# tiltGame.net
KiCad netlist of a schematic drawn in EAGLE
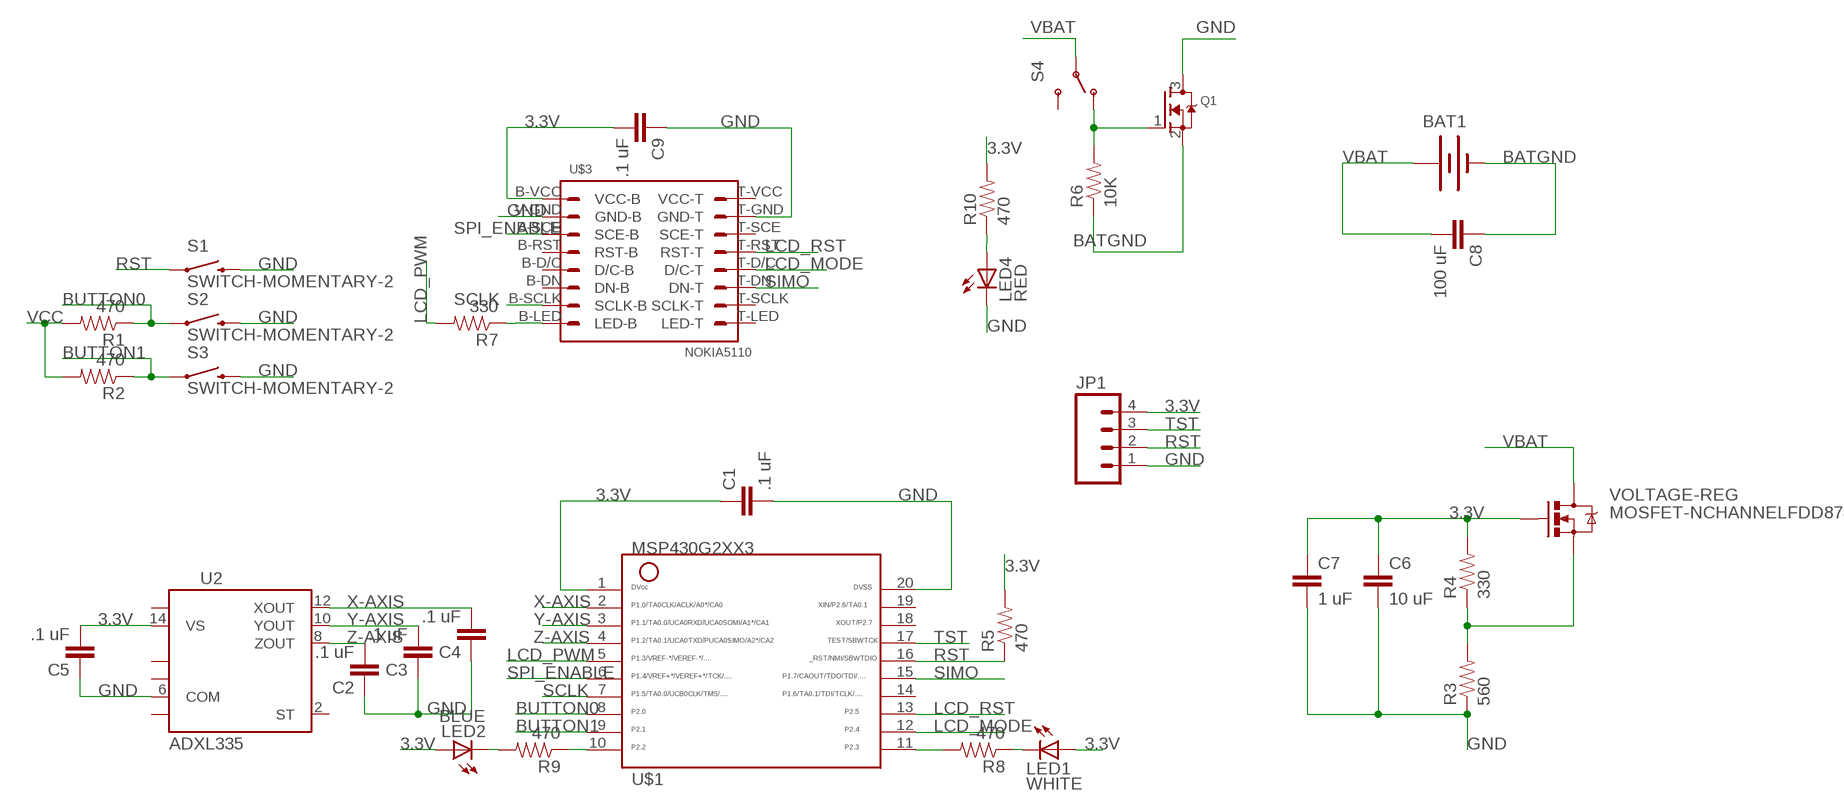
[diagram p0: schematic, sheet 1]

(export (version "E")
  (design (tool "Eeschema 10.0.6"))
  (components
    (comp (ref "BAT1")
      (value "BATTERY9V")
      (footprint "eagle-import:BATTCON_9V")
      (libsource (lib "eagle-import") (part "BATTERY9V"))
    )
    (comp (ref "C1")
      (value ".1 uF")
      (footprint "eagle-import:0805")
      (libsource (lib "eagle-import") (part "CAP0805"))
    )
    (comp (ref "C2")
      (value ".1 uF")
      (footprint "eagle-import:0805")
      (libsource (lib "eagle-import") (part "CAP0805"))
    )
    (comp (ref "C3")
      (value ".1 uF")
      (footprint "eagle-import:0805")
      (libsource (lib "eagle-import") (part "CAP0805"))
    )
    (comp (ref "C4")
      (value ".1 uF")
      (footprint "eagle-import:0805")
      (libsource (lib "eagle-import") (part "CAP0805"))
    )
    (comp (ref "C5")
      (value ".1 uF")
      (footprint "eagle-import:0805")
      (libsource (lib "eagle-import") (part "CAP0805"))
    )
    (comp (ref "C6")
      (value "10 uF")
      (footprint "eagle-import:0805")
      (libsource (lib "eagle-import") (part "CAP0805"))
    )
    (comp (ref "C7")
      (value "1 uF")
      (footprint "eagle-import:0805")
      (libsource (lib "eagle-import") (part "CAP0805"))
    )
    (comp (ref "C8")
      (value "100 uF")
      (footprint "eagle-import:0805")
      (libsource (lib "eagle-import") (part "CAP0805"))
    )
    (comp (ref "C9")
      (value ".1 uF")
      (footprint "eagle-import:0805")
      (libsource (lib "eagle-import") (part "CAP0805"))
    )
    (comp (ref "JP1")
      (value "M041X04_NO_SILK")
      (footprint "eagle-import:1X04_NO_SILK")
      (libsource (lib "eagle-import") (part "M041X04_NO_SILK"))
    )
    (comp (ref "LED1")
      (value "WHITE")
      (footprint "eagle-import:LED-1206")
      (libsource (lib "eagle-import") (part "LED1206"))
    )
    (comp (ref "LED2")
      (value "BLUE")
      (footprint "eagle-import:LED-1206")
      (libsource (lib "eagle-import") (part "LED1206"))
    )
    (comp (ref "LED4")
      (value "RED")
      (footprint "eagle-import:LED-1206")
      (libsource (lib "eagle-import") (part "LED1206"))
    )
    (comp (ref "Q1")
      (value "MOSFET-NWAVE")
      (footprint "eagle-import:SOT23-W")
      (libsource (lib "eagle-import") (part "MOSFET-NWAVE"))
    )
    (comp (ref "R1")
      (value "470")
      (footprint "eagle-import:0805")
      (libsource (lib "eagle-import") (part "RESISTOR0805-RES"))
    )
    (comp (ref "R2")
      (value "470")
      (footprint "eagle-import:0805")
      (libsource (lib "eagle-import") (part "RESISTOR0805-RES"))
    )
    (comp (ref "R3")
      (value "560")
      (footprint "eagle-import:0805")
      (libsource (lib "eagle-import") (part "RESISTOR0805-RES"))
    )
    (comp (ref "R4")
      (value "330")
      (footprint "eagle-import:0805")
      (libsource (lib "eagle-import") (part "RESISTOR0805-RES"))
    )
    (comp (ref "R5")
      (value "470")
      (footprint "eagle-import:0805")
      (libsource (lib "eagle-import") (part "RESISTOR0805-RES"))
    )
    (comp (ref "R6")
      (value "10K")
      (footprint "eagle-import:0805")
      (libsource (lib "eagle-import") (part "RESISTOR0805-RES"))
    )
    (comp (ref "R7")
      (value "330")
      (footprint "eagle-import:0805")
      (libsource (lib "eagle-import") (part "RESISTOR0805-RES"))
    )
    (comp (ref "R8")
      (value "470")
      (footprint "eagle-import:0805")
      (libsource (lib "eagle-import") (part "RESISTOR0805-RES"))
    )
    (comp (ref "R9")
      (value "470")
      (footprint "eagle-import:0805")
      (libsource (lib "eagle-import") (part "RESISTOR0805-RES"))
    )
    (comp (ref "R10")
      (value "470")
      (footprint "eagle-import:0805")
      (libsource (lib "eagle-import") (part "RESISTOR0805-RES"))
    )
    (comp (ref "S1")
      (value "SWITCH-MOMENTARY-2")
      (footprint "eagle-import:TACTILE_PANISONIC")
      (libsource (lib "eagle-import") (part "SWITCH-MOMENTARY-2"))
    )
    (comp (ref "S2")
      (value "SWITCH-MOMENTARY-2")
      (footprint "eagle-import:TACTILE_PANISONIC")
      (libsource (lib "eagle-import") (part "SWITCH-MOMENTARY-2"))
    )
    (comp (ref "S3")
      (value "SWITCH-MOMENTARY-2")
      (footprint "eagle-import:TACTILE_PANISONIC")
      (libsource (lib "eagle-import") (part "SWITCH-MOMENTARY-2"))
    )
    (comp (ref "S4")
      (value "SWITCH-SPDTPTH")
      (footprint "eagle-import:SWITCH-SPDT")
      (libsource (lib "eagle-import") (part "SWITCH-SPDTPTH"))
    )
    (comp (ref "U$1")
      (value "MSP430G2XX3TSSOP")
      (footprint "eagle-import:PW20")
      (libsource (lib "eagle-import") (part "MSP430G2XX3TSSOP"))
    )
    (comp (ref "U$3")
      (value "NOKIA5110")
      (footprint "eagle-import:NOKIA5110")
      (libsource (lib "eagle-import") (part "NOKIA5110"))
    )
    (comp (ref "U2")
      (value "ADXL335")
      (footprint "eagle-import:LFCSP-16")
      (libsource (lib "eagle-import") (part "ADXL335"))
    )
    (comp (ref "VOLTAGE-REG")
      (value "MOSFET-NCHANNELFDD8780")
      (footprint "eagle-import:DPAK")
      (libsource (lib "eagle-import") (part "MOSFET-NCHANNELFDD8780"))
    )
  )
  (nets
    (net (code "1") (name "/3.3V") (class "Default")
      (node (ref "C1") (pin "1") (pinfunction "1_1") (pintype "passive"))
      (node (ref "C5") (pin "2") (pinfunction "2_2") (pintype "passive"))
      (node (ref "C6") (pin "1") (pinfunction "1_1") (pintype "passive"))
      (node (ref "C7") (pin "1") (pinfunction "1_1") (pintype "passive"))
      (node (ref "C9") (pin "2") (pinfunction "2_2") (pintype "passive"))
      (node (ref "JP1") (pin "4") (pinfunction "4_4") (pintype "passive"))
      (node (ref "LED1") (pin "A") (pinfunction "A_A") (pintype "passive"))
      (node (ref "LED2") (pin "A") (pinfunction "A_A") (pintype "passive"))
      (node (ref "R10") (pin "2") (pinfunction "2_2") (pintype "passive"))
      (node (ref "R4") (pin "2") (pinfunction "2_2") (pintype "passive"))
      (node (ref "R5") (pin "2") (pinfunction "2_2") (pintype "passive"))
      (node (ref "U$1") (pin "1") (pinfunction "1_1") (pintype "bidirectional"))
      (node (ref "U$3") (pin "B-VCC") (pinfunction "VCC-B_B-VCC") (pintype "bidirectional"))
      (node (ref "U2") (pin "14") (pinfunction "VS_14") (pintype "bidirectional"))
      (node (ref "VOLTAGE-REG") (pin "3") (pinfunction "G-3_3") (pintype "passive"))
    )
    (net (code "2") (name "/BATGND") (class "Default")
      (node (ref "BAT1") (pin "-") (pinfunction "-_-") (pintype "power_in"))
      (node (ref "C8") (pin "1") (pinfunction "1_1") (pintype "passive"))
      (node (ref "Q1") (pin "2") (pinfunction "S_2") (pintype "bidirectional"))
      (node (ref "R6") (pin "1") (pinfunction "1_1") (pintype "passive"))
    )
    (net (code "3") (name "/BUTTON0") (class "Default")
      (node (ref "R1") (pin "1") (pinfunction "1_1") (pintype "passive"))
      (node (ref "S2") (pin "1") (pinfunction "1_1") (pintype "passive"))
      (node (ref "U$1") (pin "8") (pinfunction "8_8") (pintype "bidirectional"))
    )
    (net (code "4") (name "/BUTTON1") (class "Default")
      (node (ref "R2") (pin "1") (pinfunction "1_1") (pintype "passive"))
      (node (ref "S3") (pin "1") (pinfunction "1_1") (pintype "passive"))
      (node (ref "U$1") (pin "9") (pinfunction "9_9") (pintype "bidirectional"))
    )
    (net (code "5") (name "/GND") (class "Default")
      (node (ref "C1") (pin "2") (pinfunction "2_2") (pintype "passive"))
      (node (ref "C2") (pin "1") (pinfunction "1_1") (pintype "passive"))
      (node (ref "C3") (pin "1") (pinfunction "1_1") (pintype "passive"))
      (node (ref "C4") (pin "1") (pinfunction "1_1") (pintype "passive"))
      (node (ref "C5") (pin "1") (pinfunction "1_1") (pintype "passive"))
      (node (ref "C6") (pin "2") (pinfunction "2_2") (pintype "passive"))
      (node (ref "C7") (pin "2") (pinfunction "2_2") (pintype "passive"))
      (node (ref "C9") (pin "1") (pinfunction "1_1") (pintype "passive"))
      (node (ref "JP1") (pin "1") (pinfunction "1_1") (pintype "passive"))
      (node (ref "LED4") (pin "C") (pinfunction "C_C") (pintype "passive"))
      (node (ref "Q1") (pin "3") (pinfunction "D_3") (pintype "bidirectional"))
      (node (ref "R3") (pin "1") (pinfunction "1_1") (pintype "passive"))
      (node (ref "S1") (pin "2") (pinfunction "2_2") (pintype "passive"))
      (node (ref "S2") (pin "2") (pinfunction "2_2") (pintype "passive"))
      (node (ref "S3") (pin "2") (pinfunction "2_2") (pintype "passive"))
      (node (ref "U$1") (pin "20") (pinfunction "20_20") (pintype "bidirectional"))
      (node (ref "U$3") (pin "T-GND") (pinfunction "GND-T_T-GND") (pintype "bidirectional"))
      (node (ref "U$3") (pin "V-GND") (pinfunction "GND-B_V-GND") (pintype "bidirectional"))
      (node (ref "U2") (pin "6") (pinfunction "COM_6") (pintype "bidirectional"))
    )
    (net (code "6") (name "/LCD_MODE") (class "Default")
      (node (ref "U$1") (pin "12") (pinfunction "12_12") (pintype "bidirectional"))
      (node (ref "U$3") (pin "T-D/C") (pinfunction "D/C-T_T-D/C") (pintype "bidirectional"))
    )
    (net (code "7") (name "/LCD_PWM") (class "Default")
      (node (ref "R7") (pin "2") (pinfunction "2_2") (pintype "passive"))
      (node (ref "U$1") (pin "5") (pinfunction "5_5") (pintype "bidirectional"))
    )
    (net (code "8") (name "/LCD_RST") (class "Default")
      (node (ref "U$1") (pin "13") (pinfunction "13_13") (pintype "bidirectional"))
      (node (ref "U$3") (pin "T-RST") (pinfunction "RST-T_T-RST") (pintype "bidirectional"))
    )
    (net (code "9") (name "/RST") (class "Default")
      (node (ref "JP1") (pin "2") (pinfunction "2_2") (pintype "passive"))
      (node (ref "R5") (pin "1") (pinfunction "1_1") (pintype "passive"))
      (node (ref "S1") (pin "1") (pinfunction "1_1") (pintype "passive"))
      (node (ref "U$1") (pin "16") (pinfunction "16_16") (pintype "bidirectional"))
    )
    (net (code "10") (name "/SCLK") (class "Default")
      (node (ref "U$1") (pin "7") (pinfunction "7_7") (pintype "bidirectional"))
      (node (ref "U$3") (pin "B-SCLK") (pinfunction "SCLK-B_B-SCLK") (pintype "bidirectional"))
    )
    (net (code "11") (name "/SIMO") (class "Default")
      (node (ref "U$1") (pin "15") (pinfunction "15_15") (pintype "bidirectional"))
      (node (ref "U$3") (pin "T-DN") (pinfunction "DN-T_T-DN") (pintype "bidirectional"))
    )
    (net (code "12") (name "/SPI_ENABLE") (class "Default")
      (node (ref "U$1") (pin "6") (pinfunction "6_6") (pintype "bidirectional"))
      (node (ref "U$3") (pin "B-SCE") (pinfunction "SCE-B_B-SCE") (pintype "bidirectional"))
    )
    (net (code "13") (name "/TST") (class "Default")
      (node (ref "JP1") (pin "3") (pinfunction "3_3") (pintype "passive"))
      (node (ref "U$1") (pin "17") (pinfunction "17_17") (pintype "bidirectional"))
    )
    (net (code "14") (name "/VBAT") (class "Default")
      (node (ref "BAT1") (pin "+") (pinfunction "+_+") (pintype "power_in"))
      (node (ref "C8") (pin "2") (pinfunction "2_2") (pintype "passive"))
      (node (ref "S4") (pin "2") (pinfunction "P_2") (pintype "passive"))
      (node (ref "VOLTAGE-REG") (pin "2") (pinfunction "D-2_2") (pintype "passive"))
    )
    (net (code "15") (name "/VCC") (class "Default")
      (node (ref "R1") (pin "2") (pinfunction "2_2") (pintype "passive"))
      (node (ref "R2") (pin "2") (pinfunction "2_2") (pintype "passive"))
    )
    (net (code "16") (name "/X-AXIS") (class "Default")
      (node (ref "C4") (pin "2") (pinfunction "2_2") (pintype "passive"))
      (node (ref "U$1") (pin "2") (pinfunction "2_2") (pintype "bidirectional"))
      (node (ref "U2") (pin "12") (pinfunction "XOUT_12") (pintype "bidirectional"))
    )
    (net (code "17") (name "/Y-AXIS") (class "Default")
      (node (ref "C3") (pin "2") (pinfunction "2_2") (pintype "passive"))
      (node (ref "U$1") (pin "3") (pinfunction "3_3") (pintype "bidirectional"))
      (node (ref "U2") (pin "10") (pinfunction "YOUT_10") (pintype "bidirectional"))
    )
    (net (code "18") (name "/Z-AXIS") (class "Default")
      (node (ref "C2") (pin "2") (pinfunction "2_2") (pintype "passive"))
      (node (ref "U$1") (pin "4") (pinfunction "4_4") (pintype "bidirectional"))
      (node (ref "U2") (pin "8") (pinfunction "ZOUT_8") (pintype "bidirectional"))
    )
    (net (code "19") (name "Net-(LED1-PadC)") (class "Default")
      (node (ref "LED1") (pin "C") (pinfunction "C_C") (pintype "passive"))
      (node (ref "R8") (pin "1") (pinfunction "1_1") (pintype "passive"))
    )
    (net (code "20") (name "Net-(LED2-PadC)") (class "Default")
      (node (ref "LED2") (pin "C") (pinfunction "C_C") (pintype "passive"))
      (node (ref "R9") (pin "2") (pinfunction "2_2") (pintype "passive"))
    )
    (net (code "21") (name "Net-(LED4-PadA)") (class "Default")
      (node (ref "LED4") (pin "A") (pinfunction "A_A") (pintype "passive"))
      (node (ref "R10") (pin "1") (pinfunction "1_1") (pintype "passive"))
    )
    (net (code "22") (name "Net-(Q1-G)") (class "Default")
      (node (ref "Q1") (pin "1") (pinfunction "G_1") (pintype "bidirectional"))
      (node (ref "R6") (pin "2") (pinfunction "2_2") (pintype "passive"))
      (node (ref "S4") (pin "1") (pinfunction "O_1") (pintype "passive"))
    )
    (net (code "23") (name "Net-(R8-Pad2)") (class "Default")
      (node (ref "R8") (pin "2") (pinfunction "2_2") (pintype "passive"))
      (node (ref "U$1") (pin "11") (pinfunction "11_11") (pintype "bidirectional"))
    )
    (net (code "24") (name "Net-(R9-Pad1)") (class "Default")
      (node (ref "R9") (pin "1") (pinfunction "1_1") (pintype "passive"))
      (node (ref "U$1") (pin "10") (pinfunction "10_10") (pintype "bidirectional"))
    )
    (net (code "25") (name "Net-(U$3-LED-B)") (class "Default")
      (node (ref "R7") (pin "1") (pinfunction "1_1") (pintype "passive"))
      (node (ref "U$3") (pin "B-LED") (pinfunction "LED-B_B-LED") (pintype "bidirectional"))
    )
    (net (code "26") (name "Net-(VOLTAGE-REG-S-1)") (class "Default")
      (node (ref "R3") (pin "2") (pinfunction "2_2") (pintype "passive"))
      (node (ref "R4") (pin "1") (pinfunction "1_1") (pintype "passive"))
      (node (ref "VOLTAGE-REG") (pin "1") (pinfunction "S-1_1") (pintype "passive"))
    )
    (net (code "27") (name "unconnected-(S4-S-Pad3)") (class "Default")
      (node (ref "S4") (pin "3") (pinfunction "S_3") (pintype "passive"))
    )
    (net (code "28") (name "unconnected-(U$1-Pad14)") (class "Default")
      (node (ref "U$1") (pin "14") (pinfunction "14_14") (pintype "bidirectional"))
    )
    (net (code "29") (name "unconnected-(U$1-Pad18)") (class "Default")
      (node (ref "U$1") (pin "18") (pinfunction "18_18") (pintype "bidirectional"))
    )
    (net (code "30") (name "unconnected-(U$1-Pad19)") (class "Default")
      (node (ref "U$1") (pin "19") (pinfunction "19_19") (pintype "bidirectional"))
    )
    (net (code "31") (name "unconnected-(U$3-DN-B-PadB-DN)") (class "Default")
      (node (ref "U$3") (pin "B-DN") (pinfunction "DN-B_B-DN") (pintype "bidirectional"))
    )
    (net (code "32") (name "unconnected-(U$3-D{slash}C-B-PadB-D{slash}C)") (class "Default")
      (node (ref "U$3") (pin "B-D/C") (pinfunction "D/C-B_B-D/C") (pintype "bidirectional"))
    )
    (net (code "33") (name "unconnected-(U$3-LED-T-PadT-LED)") (class "Default")
      (node (ref "U$3") (pin "T-LED") (pinfunction "LED-T_T-LED") (pintype "bidirectional"))
    )
    (net (code "34") (name "unconnected-(U$3-RST-B-PadB-RST)") (class "Default")
      (node (ref "U$3") (pin "B-RST") (pinfunction "RST-B_B-RST") (pintype "bidirectional"))
    )
    (net (code "35") (name "unconnected-(U$3-SCE-T-PadT-SCE)") (class "Default")
      (node (ref "U$3") (pin "T-SCE") (pinfunction "SCE-T_T-SCE") (pintype "bidirectional"))
    )
    (net (code "36") (name "unconnected-(U$3-SCLK-T-PadT-SCLK)") (class "Default")
      (node (ref "U$3") (pin "T-SCLK") (pinfunction "SCLK-T_T-SCLK") (pintype "bidirectional"))
    )
    (net (code "37") (name "unconnected-(U$3-VCC-T-PadT-VCC)") (class "Default")
      (node (ref "U$3") (pin "T-VCC") (pinfunction "VCC-T_T-VCC") (pintype "bidirectional"))
    )
    (net (code "38") (name "unconnected-(U2-COM-Pad3)") (class "Default")
      (node (ref "U2") (pin "3") (pinfunction "COM_3") (pintype "bidirectional"))
    )
    (net (code "39") (name "unconnected-(U2-COM-Pad5)") (class "Default")
      (node (ref "U2") (pin "5") (pinfunction "COM_5") (pintype "bidirectional"))
    )
    (net (code "40") (name "unconnected-(U2-COM-Pad7)") (class "Default")
      (node (ref "U2") (pin "7") (pinfunction "COM_7") (pintype "bidirectional"))
    )
    (net (code "41") (name "unconnected-(U2-ST-Pad2)") (class "Default")
      (node (ref "U2") (pin "2") (pinfunction "ST_2") (pintype "bidirectional"))
    )
    (net (code "42") (name "unconnected-(U2-VS-Pad15)") (class "Default")
      (node (ref "U2") (pin "15") (pinfunction "VS_15") (pintype "bidirectional"))
    )
  )
)
